# arduino_smartsensor_shield.net
KiCad netlist of a schematic drawn in EAGLE
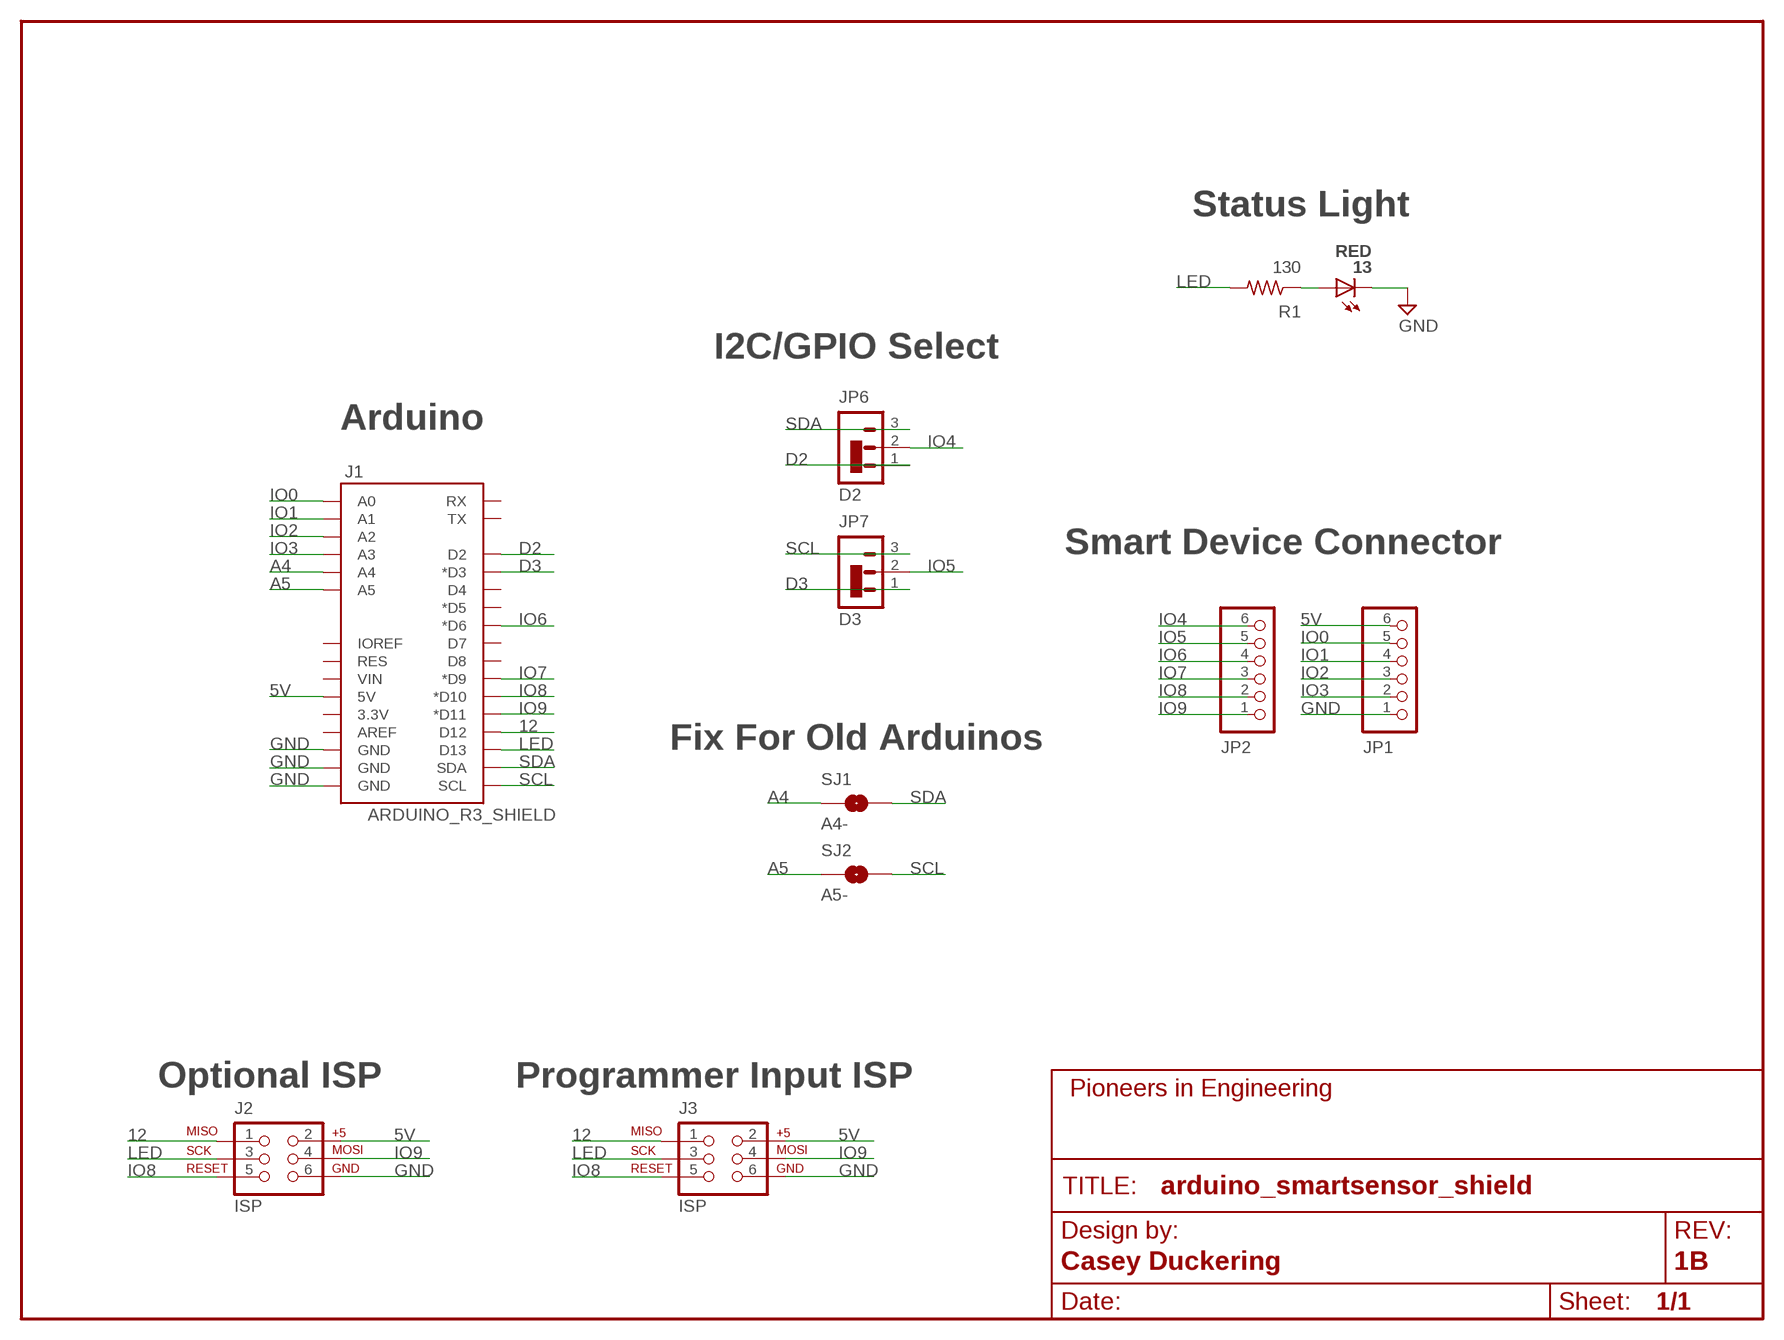
[diagram p0: schematic, sheet 1]

(export (version "E")
  (design (tool "Eeschema 10.0.6"))
  (components
    (comp (ref "13")
      (value "RED")
      (footprint "eagle-import:LED-0805")
      (libsource (lib "eagle-import") (part "LED0805"))
    )
    (comp (ref "J1")
      (value "ARDUINO_R3_SHIELD")
      (footprint "eagle-import:UNO_R3_SHIELD")
      (libsource (lib "eagle-import") (part "ARDUINO_R3_SHIELD"))
    )
    (comp (ref "J2")
      (value "ISP")
      (footprint "eagle-import:2X3")
      (libsource (lib "eagle-import") (part "AVR_SPI_PRG_6PTH"))
    )
    (comp (ref "J3")
      (value "ISP")
      (footprint "eagle-import:2X3")
      (libsource (lib "eagle-import") (part "AVR_SPI_PRG_6PTH"))
    )
    (comp (ref "JP1")
      (value "PINHD-1X6STRAIN-RELIEF")
      (footprint "eagle-import:1X06-STRAINRELIEF")
      (libsource (lib "eagle-import") (part "PINHD-1X6STRAIN-RELIEF"))
    )
    (comp (ref "JP2")
      (value "PINHD-1X6")
      (footprint "eagle-import:1X06")
      (fields (field (name "PARTNUMBER") "965"))
      (libsource (lib "eagle-import") (part "PINHD-1X6"))
    )
    (comp (ref "JP6")
      (value "D2")
      (footprint "eagle-import:1X03-JMP-OPTION")
      (libsource (lib "eagle-import") (part "JMP-OPTION"))
    )
    (comp (ref "JP7")
      (value "D3")
      (footprint "eagle-import:1X03-JMP-OPTION")
      (libsource (lib "eagle-import") (part "JMP-OPTION"))
    )
    (comp (ref "R1")
      (value "130")
      (footprint "eagle-import:R0603")
      (libsource (lib "eagle-import") (part "R-US_R0603"))
    )
    (comp (ref "SJ1")
      (value "A4-")
      (footprint "eagle-import:SJ_2S-NO")
      (libsource (lib "eagle-import") (part "SOLDERJUMPERNO"))
    )
    (comp (ref "SJ2")
      (value "A5-")
      (footprint "eagle-import:SJ_2S-NO")
      (libsource (lib "eagle-import") (part "SOLDERJUMPERNO"))
    )
  )
  (nets
    (net (code "1") (name "/5V") (class "Default")
      (node (ref "J1") (pin "5V") (pinfunction "5V_5V") (pintype "bidirectional"))
      (node (ref "J2") (pin "2") (pinfunction "2_2") (pintype "passive"))
      (node (ref "J3") (pin "2") (pinfunction "2_2") (pintype "passive"))
      (node (ref "JP1") (pin "6") (pinfunction "6_6") (pintype "passive"))
    )
    (net (code "2") (name "/12") (class "Default")
      (node (ref "J1") (pin "D12") (pinfunction "D12_D12") (pintype "bidirectional"))
      (node (ref "J2") (pin "1") (pinfunction "1_1") (pintype "passive"))
      (node (ref "J3") (pin "1") (pinfunction "1_1") (pintype "passive"))
    )
    (net (code "3") (name "/A4") (class "Default")
      (node (ref "J1") (pin "A4") (pinfunction "A4_A4") (pintype "bidirectional"))
      (node (ref "SJ1") (pin "1") (pinfunction "1_1") (pintype "passive"))
    )
    (net (code "4") (name "/A5") (class "Default")
      (node (ref "J1") (pin "A5") (pinfunction "A5_A5") (pintype "bidirectional"))
      (node (ref "SJ2") (pin "1") (pinfunction "1_1") (pintype "passive"))
    )
    (net (code "5") (name "/D2") (class "Default")
      (node (ref "J1") (pin "D2") (pinfunction "D2_D2") (pintype "bidirectional"))
      (node (ref "JP6") (pin "1") (pinfunction "1_1") (pintype "passive"))
    )
    (net (code "6") (name "/D3") (class "Default")
      (node (ref "J1") (pin "D3") (pinfunction "*D3_D3") (pintype "bidirectional"))
      (node (ref "JP7") (pin "1") (pinfunction "1_1") (pintype "passive"))
    )
    (net (code "7") (name "/IO0") (class "Default")
      (node (ref "J1") (pin "A0") (pinfunction "A0_A0") (pintype "bidirectional"))
      (node (ref "JP1") (pin "5") (pinfunction "5_5") (pintype "passive"))
    )
    (net (code "8") (name "/IO1") (class "Default")
      (node (ref "J1") (pin "A1") (pinfunction "A1_A1") (pintype "bidirectional"))
      (node (ref "JP1") (pin "4") (pinfunction "4_4") (pintype "passive"))
    )
    (net (code "9") (name "/IO2") (class "Default")
      (node (ref "J1") (pin "A2") (pinfunction "A2_A2") (pintype "bidirectional"))
      (node (ref "JP1") (pin "3") (pinfunction "3_3") (pintype "passive"))
    )
    (net (code "10") (name "/IO3") (class "Default")
      (node (ref "J1") (pin "A3") (pinfunction "A3_A3") (pintype "bidirectional"))
      (node (ref "JP1") (pin "2") (pinfunction "2_2") (pintype "passive"))
    )
    (net (code "11") (name "/IO4") (class "Default")
      (node (ref "JP2") (pin "6") (pinfunction "6_6") (pintype "passive"))
      (node (ref "JP6") (pin "2") (pinfunction "COMMON_2") (pintype "passive"))
    )
    (net (code "12") (name "/IO5") (class "Default")
      (node (ref "JP2") (pin "5") (pinfunction "5_5") (pintype "passive"))
      (node (ref "JP7") (pin "2") (pinfunction "COMMON_2") (pintype "passive"))
    )
    (net (code "13") (name "/IO6") (class "Default")
      (node (ref "J1") (pin "D6") (pinfunction "*D6_D6") (pintype "bidirectional"))
      (node (ref "JP2") (pin "4") (pinfunction "4_4") (pintype "passive"))
    )
    (net (code "14") (name "/IO7") (class "Default")
      (node (ref "J1") (pin "D9") (pinfunction "*D9_D9") (pintype "bidirectional"))
      (node (ref "JP2") (pin "3") (pinfunction "3_3") (pintype "passive"))
    )
    (net (code "15") (name "/IO8") (class "Default")
      (node (ref "J1") (pin "D10") (pinfunction "*D10_D10") (pintype "bidirectional"))
      (node (ref "J2") (pin "5") (pinfunction "5_5") (pintype "passive"))
      (node (ref "J3") (pin "5") (pinfunction "5_5") (pintype "passive"))
      (node (ref "JP2") (pin "2") (pinfunction "2_2") (pintype "passive"))
    )
    (net (code "16") (name "/IO9") (class "Default")
      (node (ref "J1") (pin "D11") (pinfunction "*D11_D11") (pintype "bidirectional"))
      (node (ref "J2") (pin "4") (pinfunction "4_4") (pintype "passive"))
      (node (ref "J3") (pin "4") (pinfunction "4_4") (pintype "passive"))
      (node (ref "JP2") (pin "1") (pinfunction "1_1") (pintype "passive"))
    )
    (net (code "17") (name "/LED") (class "Default")
      (node (ref "J1") (pin "D13") (pinfunction "D13_D13") (pintype "bidirectional"))
      (node (ref "J2") (pin "3") (pinfunction "3_3") (pintype "passive"))
      (node (ref "J3") (pin "3") (pinfunction "3_3") (pintype "passive"))
      (node (ref "R1") (pin "2") (pinfunction "2_2") (pintype "passive"))
    )
    (net (code "18") (name "/SCL") (class "Default")
      (node (ref "J1") (pin "SCL") (pinfunction "SCL_SCL") (pintype "bidirectional"))
      (node (ref "JP7") (pin "3") (pinfunction "3_3") (pintype "passive"))
      (node (ref "SJ2") (pin "2") (pinfunction "2_2") (pintype "passive"))
    )
    (net (code "19") (name "/SDA") (class "Default")
      (node (ref "J1") (pin "SDA") (pinfunction "SDA_SDA") (pintype "bidirectional"))
      (node (ref "JP6") (pin "3") (pinfunction "3_3") (pintype "passive"))
      (node (ref "SJ1") (pin "2") (pinfunction "2_2") (pintype "passive"))
    )
    (net (code "20") (name "GND") (class "Default")
      (node (ref "13") (pin "C") (pinfunction "C_C") (pintype "passive"))
      (node (ref "J1") (pin "GND@0") (pinfunction "GND_GND@0") (pintype "bidirectional"))
      (node (ref "J1") (pin "GND@1") (pinfunction "GND_GND@1") (pintype "bidirectional"))
      (node (ref "J1") (pin "GND@2") (pinfunction "GND_GND@2") (pintype "bidirectional"))
      (node (ref "J2") (pin "6") (pinfunction "6_6") (pintype "passive"))
      (node (ref "J3") (pin "6") (pinfunction "6_6") (pintype "passive"))
      (node (ref "JP1") (pin "1") (pinfunction "1_1") (pintype "passive"))
    )
    (net (code "21") (name "Net-(13-PadA)") (class "Default")
      (node (ref "13") (pin "A") (pinfunction "A_A") (pintype "passive"))
      (node (ref "R1") (pin "1") (pinfunction "1_1") (pintype "passive"))
    )
    (net (code "22") (name "unconnected-(J1-*D5-PadD5)") (class "Default")
      (node (ref "J1") (pin "D5") (pinfunction "*D5_D5") (pintype "bidirectional"))
    )
    (net (code "23") (name "unconnected-(J1-Pad3.3V)") (class "Default")
      (node (ref "J1") (pin "3.3V") (pinfunction "3.3V_3.3V") (pintype "bidirectional"))
    )
    (net (code "24") (name "unconnected-(J1-PadAREF)") (class "Default")
      (node (ref "J1") (pin "AREF") (pinfunction "AREF_AREF") (pintype "bidirectional"))
    )
    (net (code "25") (name "unconnected-(J1-PadD4)") (class "Default")
      (node (ref "J1") (pin "D4") (pinfunction "D4_D4") (pintype "bidirectional"))
    )
    (net (code "26") (name "unconnected-(J1-PadD7)") (class "Default")
      (node (ref "J1") (pin "D7") (pinfunction "D7_D7") (pintype "bidirectional"))
    )
    (net (code "27") (name "unconnected-(J1-PadD8)") (class "Default")
      (node (ref "J1") (pin "D8") (pinfunction "D8_D8") (pintype "bidirectional"))
    )
    (net (code "28") (name "unconnected-(J1-PadIOREF)") (class "Default")
      (node (ref "J1") (pin "IOREF") (pinfunction "IOREF_IOREF") (pintype "bidirectional"))
    )
    (net (code "29") (name "unconnected-(J1-PadRES)") (class "Default")
      (node (ref "J1") (pin "RES") (pinfunction "RES_RES") (pintype "bidirectional"))
    )
    (net (code "30") (name "unconnected-(J1-PadRX)") (class "Default")
      (node (ref "J1") (pin "RX") (pinfunction "RX_RX") (pintype "bidirectional"))
    )
    (net (code "31") (name "unconnected-(J1-PadTX)") (class "Default")
      (node (ref "J1") (pin "TX") (pinfunction "TX_TX") (pintype "bidirectional"))
    )
    (net (code "32") (name "unconnected-(J1-PadVIN)") (class "Default")
      (node (ref "J1") (pin "VIN") (pinfunction "VIN_VIN") (pintype "bidirectional"))
    )
  )
)
